# MIni_Quadcopter.net
KiCad netlist of a schematic drawn in Altium Designer
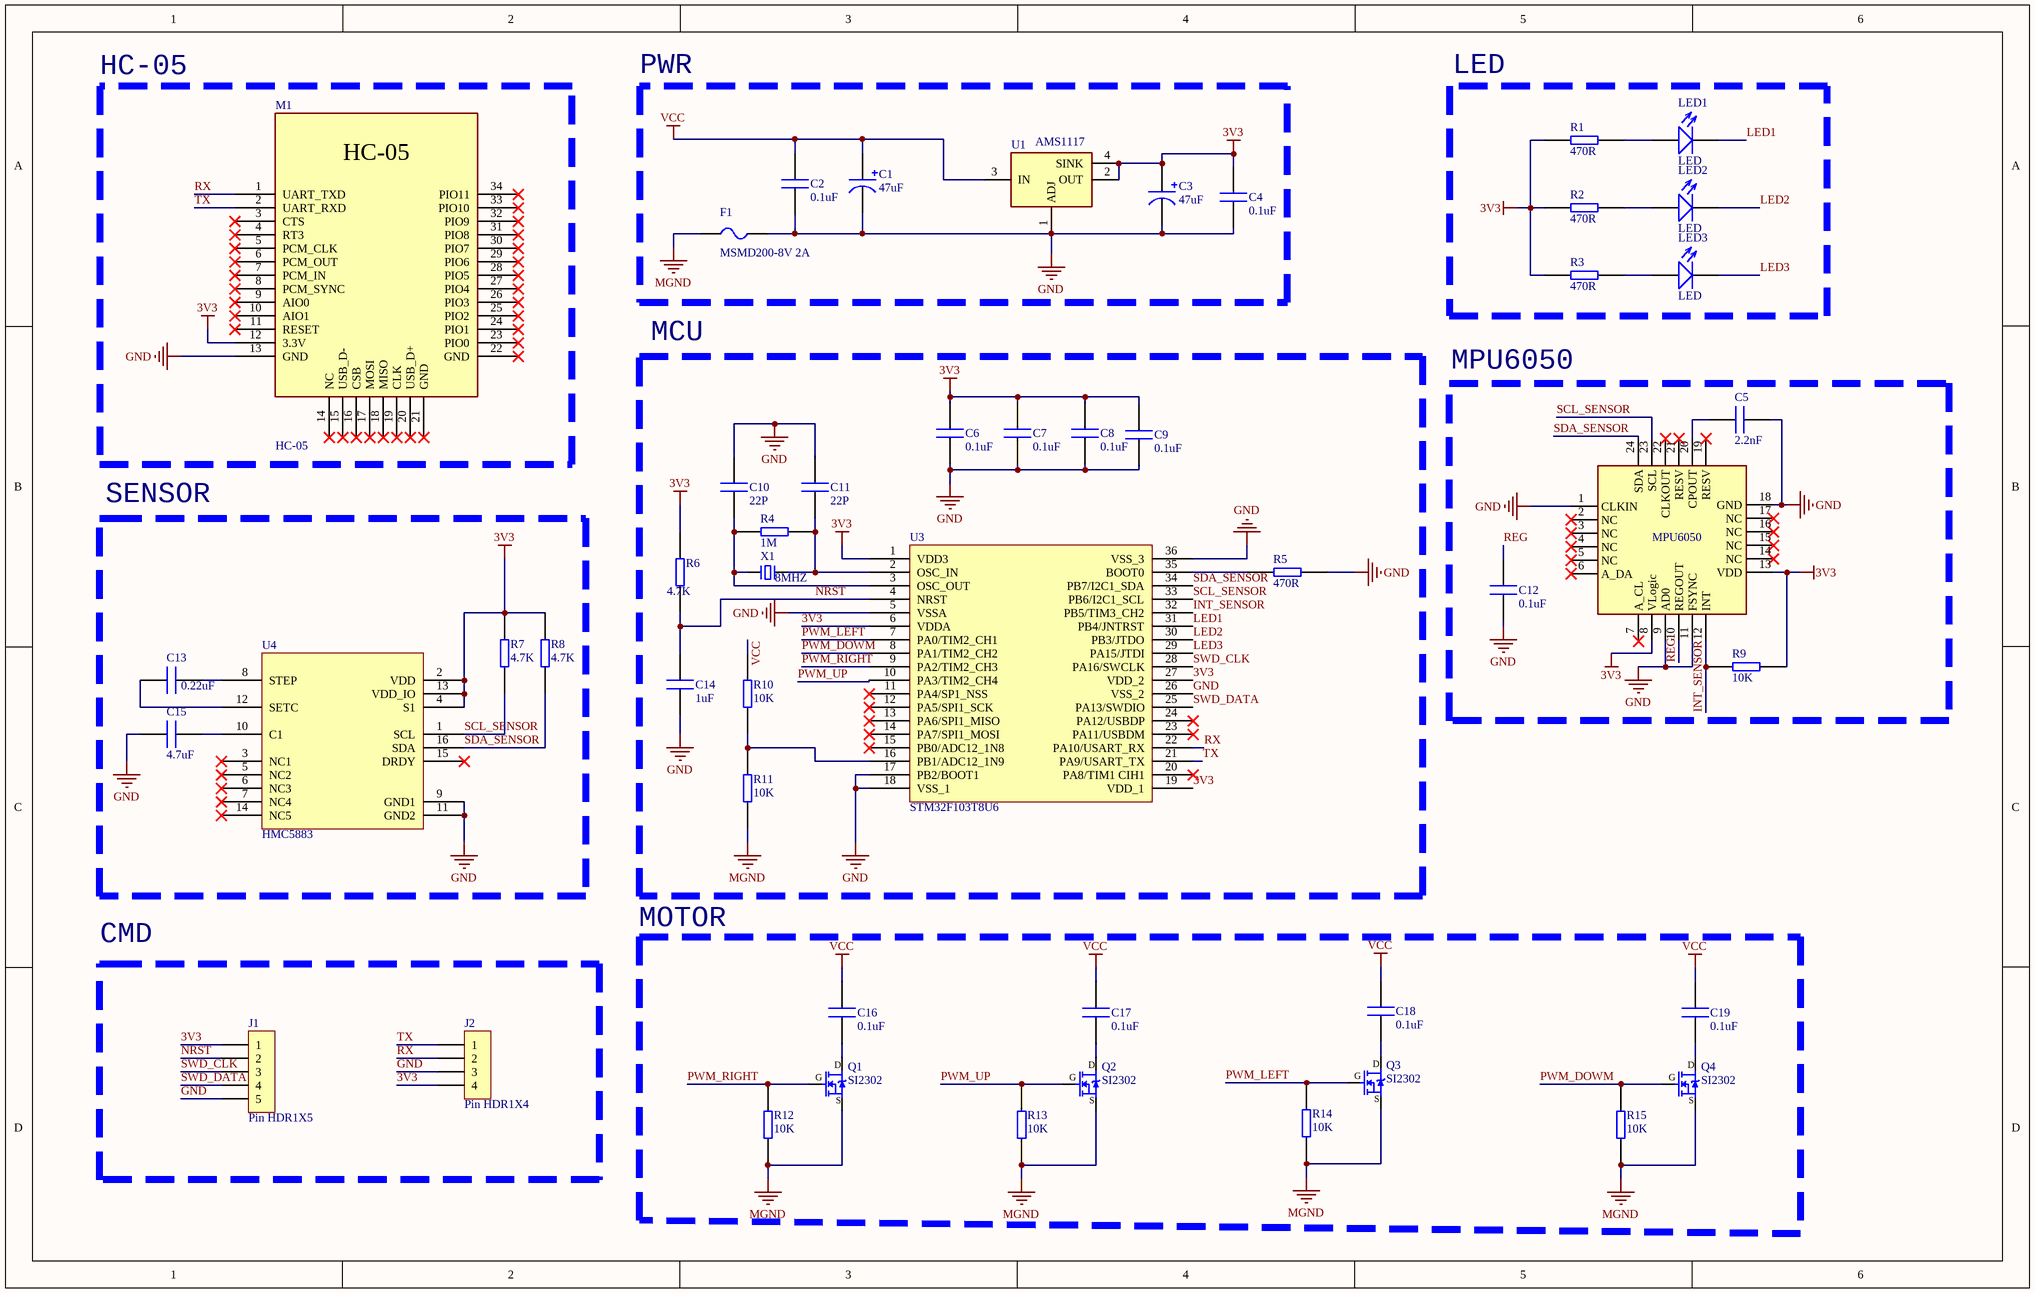
[diagram p0: MIni_Quadcopter.SchDoc]

(export (version "E")
  (design (tool "Eeschema 10.0.6"))
  (components
    (comp (ref "C1")
      (value "47uF")
      (footprint "Cap_SMD_5*5.4mm")
      (description "极性电容")
      (libsource (lib "COMMON") (part "Cap2"))
    )
    (comp (ref "C2")
      (value "0.1uF")
      (footprint "C0603")
      (description "无极电容")
      (libsource (lib "COMMON") (part "Cap1"))
    )
    (comp (ref "C3")
      (value "47uF")
      (footprint "Cap_SMD_5*5.4mm")
      (description "极性电容")
      (libsource (lib "COMMON") (part "Cap2"))
    )
    (comp (ref "C4")
      (value "0.1uF")
      (footprint "C0603")
      (description "无极电容")
      (libsource (lib "COMMON") (part "Cap1"))
    )
    (comp (ref "C5")
      (value "2.2nF")
      (footprint "C0603")
      (description "无极电容")
      (libsource (lib "COMMON") (part "Cap1"))
    )
    (comp (ref "C6")
      (value "0.1uF")
      (footprint "C0603")
      (description "无极电容")
      (libsource (lib "COMMON") (part "Cap1"))
    )
    (comp (ref "C7")
      (value "0.1uF")
      (footprint "C0603")
      (description "无极电容")
      (libsource (lib "COMMON") (part "Cap1"))
    )
    (comp (ref "C8")
      (value "0.1uF")
      (footprint "C0603")
      (description "无极电容")
      (libsource (lib "COMMON") (part "Cap1"))
    )
    (comp (ref "C9")
      (value "0.1uF")
      (footprint "C0603")
      (description "无极电容")
      (libsource (lib "COMMON") (part "Cap1"))
    )
    (comp (ref "C10")
      (value "22P")
      (footprint "C0603")
      (description "无极电容")
      (libsource (lib "COMMON") (part "Cap1"))
    )
    (comp (ref "C11")
      (value "22P")
      (footprint "C0603")
      (description "无极电容")
      (libsource (lib "COMMON") (part "Cap1"))
    )
    (comp (ref "C12")
      (value "0.1uF")
      (footprint "C0603")
      (description "无极电容")
      (libsource (lib "COMMON") (part "Cap1"))
    )
    (comp (ref "C13")
      (value "0.22uF")
      (footprint "C0603")
      (description "无极电容")
      (libsource (lib "COMMON") (part "Cap1"))
    )
    (comp (ref "C14")
      (value "1uF")
      (footprint "C0603")
      (description "无极电容")
      (libsource (lib "COMMON") (part "Cap1"))
    )
    (comp (ref "C15")
      (value "4.7uF")
      (footprint "C0603")
      (description "无极电容")
      (libsource (lib "COMMON") (part "Cap1"))
    )
    (comp (ref "C16")
      (value "0.1uF")
      (footprint "C0603")
      (description "无极电容")
      (libsource (lib "COMMON") (part "Cap1"))
    )
    (comp (ref "C17")
      (value "0.1uF")
      (footprint "C0603")
      (description "无极电容")
      (libsource (lib "COMMON") (part "Cap1"))
    )
    (comp (ref "C18")
      (value "0.1uF")
      (footprint "C0603")
      (description "无极电容")
      (libsource (lib "COMMON") (part "Cap1"))
    )
    (comp (ref "C19")
      (value "0.1uF")
      (footprint "C0603")
      (description "无极电容")
      (libsource (lib "COMMON") (part "Cap1"))
    )
    (comp (ref "F1")
      (value "MSMD200-8V 2A")
      (footprint "FU 1206")
      (description "贴片保险丝")
      (libsource (lib "COMMON") (part "FU"))
    )
    (comp (ref "J1")
      (value "Pin HDR1X5")
      (footprint "Pin HDR1X5/2mm-W")
      (libsource (lib "COMMON") (part "Pin HDR1X5"))
    )
    (comp (ref "J2")
      (value "Pin HDR1X4")
      (footprint "Pin HDR1X4/2.54mm-S")
      (libsource (lib "COMMON") (part "Pin HDR1X4"))
    )
    (comp (ref "LED1")
      (value "LED")
      (footprint "LED_0603")
      (description "发光二极管")
      (libsource (lib "COMMON") (part "LED"))
    )
    (comp (ref "LED2")
      (value "LED")
      (footprint "LED_0603")
      (description "发光二极管")
      (libsource (lib "COMMON") (part "LED"))
    )
    (comp (ref "LED3")
      (value "LED")
      (footprint "LED_0603")
      (description "发光二极管")
      (libsource (lib "COMMON") (part "LED"))
    )
    (comp (ref "M1")
      (value "HC-05")
      (footprint "HC-05")
      (description "串口蓝牙模块")
      (fields (field (name "版权归属") "源创客"))
      (libsource (lib "COMMON") (part "HC-05"))
    )
    (comp (ref "Q1")
      (value "SI2302")
      (footprint "SOT_23")
      (description "N沟道 20V/3A")
      (fields (field (name "版权归属") "源创客"))
      (libsource (lib "COMMON") (part "SI2302"))
    )
    (comp (ref "Q2")
      (value "SI2302")
      (footprint "SOT_23")
      (description "N沟道 20V/3A")
      (fields (field (name "版权归属") "源创客"))
      (libsource (lib "COMMON") (part "SI2302"))
    )
    (comp (ref "Q3")
      (value "SI2302")
      (footprint "SOT_23")
      (description "N沟道 20V/3A")
      (fields (field (name "版权归属") "源创客"))
      (libsource (lib "COMMON") (part "SI2302"))
    )
    (comp (ref "Q4")
      (value "SI2302")
      (footprint "SOT_23")
      (description "N沟道 20V/3A")
      (fields (field (name "版权归属") "源创客"))
      (libsource (lib "COMMON") (part "SI2302"))
    )
    (comp (ref "R1")
      (value "470R")
      (footprint "R0603")
      (description "普通电阻")
      (libsource (lib "COMMON") (part "Res"))
    )
    (comp (ref "R2")
      (value "470R")
      (footprint "R0603")
      (description "普通电阻")
      (libsource (lib "COMMON") (part "Res"))
    )
    (comp (ref "R3")
      (value "470R")
      (footprint "R0603")
      (description "普通电阻")
      (libsource (lib "COMMON") (part "Res"))
    )
    (comp (ref "R4")
      (value "1M")
      (footprint "R0603")
      (description "普通电阻")
      (libsource (lib "COMMON") (part "Res"))
    )
    (comp (ref "R5")
      (value "470R")
      (footprint "R0603")
      (description "普通电阻")
      (libsource (lib "COMMON") (part "Res"))
    )
    (comp (ref "R6")
      (value "4.7K")
      (footprint "R0603")
      (description "普通电阻")
      (libsource (lib "COMMON") (part "Res"))
    )
    (comp (ref "R7")
      (value "4.7K")
      (footprint "R0603")
      (description "普通电阻")
      (libsource (lib "COMMON") (part "Res"))
    )
    (comp (ref "R8")
      (value "4.7K")
      (footprint "R0603")
      (description "普通电阻")
      (libsource (lib "COMMON") (part "Res"))
    )
    (comp (ref "R9")
      (value "10K")
      (footprint "R0603")
      (description "普通电阻")
      (libsource (lib "COMMON") (part "Res"))
    )
    (comp (ref "R10")
      (value "10K")
      (footprint "R0603")
      (description "普通电阻")
      (libsource (lib "COMMON") (part "Res"))
    )
    (comp (ref "R11")
      (value "10K")
      (footprint "R0603")
      (description "普通电阻")
      (libsource (lib "COMMON") (part "Res"))
    )
    (comp (ref "R12")
      (value "10K")
      (footprint "R0603")
      (description "普通电阻")
      (libsource (lib "COMMON") (part "Res"))
    )
    (comp (ref "R13")
      (value "10K")
      (footprint "R0603")
      (description "普通电阻")
      (libsource (lib "COMMON") (part "Res"))
    )
    (comp (ref "R14")
      (value "10K")
      (footprint "R0603")
      (description "普通电阻")
      (libsource (lib "COMMON") (part "Res"))
    )
    (comp (ref "R15")
      (value "10K")
      (footprint "R0603")
      (description "普通电阻")
      (libsource (lib "COMMON") (part "Res"))
    )
    (comp (ref "U1")
      (value "AMS1117")
      (footprint "SOT_223")
      (description "稳压电源芯片降压IC")
      (libsource (lib "IC") (part "AMS1117"))
    )
    (comp (ref "U2")
      (value "MPU6050")
      (footprint "QFN-24")
      (description "六轴传感器")
      (libsource (lib "IC") (part "MPU6050"))
    )
    (comp (ref "U3")
      (value "STM32F103T8U6")
      (footprint "VFQN36_M")
      (libsource (lib "MCU") (part "STM32F103T8U6"))
    )
    (comp (ref "U4")
      (value "HMC5883")
      (footprint "LGA-16")
      (description "地磁传感器")
      (libsource (lib "IC") (part "HMC5883"))
    )
    (comp (ref "X1")
      (value "8MHZ")
      (footprint "OSC HC-49S")
      (description "2脚无源脚晶振")
      (libsource (lib "COMMON") (part "XTAL-2P"))
    )
  )
  (nets
    (net (code "1") (name "/INT_SENSOR") (class "Default")
      (node (ref "R9") (pin "1") (pinfunction "1_1") (pintype "passive"))
      (node (ref "U2") (pin "12") (pinfunction "INT_12") (pintype "passive"))
      (node (ref "U3") (pin "32") (pinfunction "PB5/TIM3_CH2_32") (pintype "passive"))
    )
    (net (code "2") (name "/LED1") (class "Default")
      (node (ref "LED1") (pin "1") (pinfunction "1_1") (pintype "passive"))
      (node (ref "U3") (pin "31") (pinfunction "PB4/JNTRST_31") (pintype "passive"))
    )
    (net (code "3") (name "/LED2") (class "Default")
      (node (ref "LED2") (pin "1") (pinfunction "1_1") (pintype "passive"))
      (node (ref "U3") (pin "30") (pinfunction "PB3/JTDO_30") (pintype "passive"))
    )
    (net (code "4") (name "/LED3") (class "Default")
      (node (ref "LED3") (pin "1") (pinfunction "1_1") (pintype "passive"))
      (node (ref "U3") (pin "29") (pinfunction "PA15/JTDI_29") (pintype "passive"))
    )
    (net (code "5") (name "/NRST") (class "Default")
      (node (ref "C14") (pin "2") (pinfunction "2_2") (pintype "passive"))
      (node (ref "J1") (pin "2") (pinfunction "2_2") (pintype "passive"))
      (node (ref "R6") (pin "1") (pinfunction "1_1") (pintype "passive"))
      (node (ref "U3") (pin "4") (pinfunction "NRST_4") (pintype "passive"))
    )
    (net (code "6") (name "/PWM_DOWM") (class "Default")
      (node (ref "Q4") (pin "1") (pinfunction "G_1") (pintype "passive"))
      (node (ref "R15") (pin "2") (pinfunction "2_2") (pintype "passive"))
      (node (ref "U3") (pin "8") (pinfunction "PA1/TIM2_CH2_8") (pintype "passive"))
    )
    (net (code "7") (name "/PWM_LEFT") (class "Default")
      (node (ref "Q3") (pin "1") (pinfunction "G_1") (pintype "passive"))
      (node (ref "R14") (pin "2") (pinfunction "2_2") (pintype "passive"))
      (node (ref "U3") (pin "7") (pinfunction "PA0/TIM2_CH1_7") (pintype "passive"))
    )
    (net (code "8") (name "/PWM_RIGHT") (class "Default")
      (node (ref "Q1") (pin "1") (pinfunction "G_1") (pintype "passive"))
      (node (ref "R12") (pin "2") (pinfunction "2_2") (pintype "passive"))
      (node (ref "U3") (pin "9") (pinfunction "PA2/TIM2_CH3_9") (pintype "passive"))
    )
    (net (code "9") (name "/PWM_UP") (class "Default")
      (node (ref "Q2") (pin "1") (pinfunction "G_1") (pintype "passive"))
      (node (ref "R13") (pin "2") (pinfunction "2_2") (pintype "passive"))
      (node (ref "U3") (pin "10") (pinfunction "PA3/TIM2_CH4_10") (pintype "passive"))
    )
    (net (code "10") (name "/REG") (class "Default")
      (node (ref "C12") (pin "1") (pinfunction "1_1") (pintype "passive"))
      (node (ref "U2") (pin "10") (pinfunction "REGOUT_10") (pintype "passive"))
    )
    (net (code "11") (name "/RX") (class "Default")
      (node (ref "J2") (pin "2") (pinfunction "2_2") (pintype "passive"))
      (node (ref "M1") (pin "1") (pinfunction "UART_TXD_1") (pintype "passive"))
      (node (ref "U3") (pin "22") (pinfunction "PA10/USART_RX_22") (pintype "passive"))
    )
    (net (code "12") (name "/SCL_SENSOR") (class "Default")
      (node (ref "R7") (pin "1") (pinfunction "1_1") (pintype "passive"))
      (node (ref "U2") (pin "23") (pinfunction "SCL_23") (pintype "passive"))
      (node (ref "U3") (pin "33") (pinfunction "PB6/I2C1_SCL_33") (pintype "passive"))
      (node (ref "U4") (pin "1") (pinfunction "SCL_1") (pintype "passive"))
    )
    (net (code "13") (name "/SDA_SENSOR") (class "Default")
      (node (ref "R8") (pin "1") (pinfunction "1_1") (pintype "passive"))
      (node (ref "U2") (pin "24") (pinfunction "SDA_24") (pintype "passive"))
      (node (ref "U3") (pin "34") (pinfunction "PB7/I2C1_SDA_34") (pintype "passive"))
      (node (ref "U4") (pin "16") (pinfunction "SDA_16") (pintype "passive"))
    )
    (net (code "14") (name "/SWD_CLK") (class "Default")
      (node (ref "J1") (pin "3") (pinfunction "3_3") (pintype "passive"))
      (node (ref "U3") (pin "28") (pinfunction "PA16/SWCLK_28") (pintype "passive"))
    )
    (net (code "15") (name "/SWD_DATA") (class "Default")
      (node (ref "J1") (pin "4") (pinfunction "4_4") (pintype "passive"))
      (node (ref "U3") (pin "25") (pinfunction "PA13/SWDIO_25") (pintype "passive"))
    )
    (net (code "16") (name "/TX") (class "Default")
      (node (ref "J2") (pin "1") (pinfunction "1_1") (pintype "passive"))
      (node (ref "M1") (pin "2") (pinfunction "UART_RXD_2") (pintype "passive"))
      (node (ref "U3") (pin "21") (pinfunction "PA9/USART_TX_21") (pintype "passive"))
    )
    (net (code "17") (name "3V3") (class "Default")
      (node (ref "C3") (pin "1") (pinfunction "1_1") (pintype "passive"))
      (node (ref "C4") (pin "2") (pinfunction "2_2") (pintype "passive"))
      (node (ref "C6") (pin "2") (pinfunction "2_2") (pintype "passive"))
      (node (ref "C7") (pin "2") (pinfunction "2_2") (pintype "passive"))
      (node (ref "C8") (pin "2") (pinfunction "2_2") (pintype "passive"))
      (node (ref "C9") (pin "2") (pinfunction "2_2") (pintype "passive"))
      (node (ref "J1") (pin "1") (pinfunction "1_1") (pintype "passive"))
      (node (ref "J2") (pin "4") (pinfunction "4_4") (pintype "passive"))
      (node (ref "M1") (pin "12") (pinfunction "3.3V_12") (pintype "passive"))
      (node (ref "R1") (pin "1") (pinfunction "1_1") (pintype "passive"))
      (node (ref "R2") (pin "1") (pinfunction "1_1") (pintype "passive"))
      (node (ref "R3") (pin "1") (pinfunction "1_1") (pintype "passive"))
      (node (ref "R6") (pin "2") (pinfunction "2_2") (pintype "passive"))
      (node (ref "R7") (pin "2") (pinfunction "2_2") (pintype "passive"))
      (node (ref "R8") (pin "2") (pinfunction "2_2") (pintype "passive"))
      (node (ref "R9") (pin "2") (pinfunction "2_2") (pintype "passive"))
      (node (ref "U1") (pin "2") (pinfunction "OUT_2") (pintype "passive"))
      (node (ref "U1") (pin "4") (pinfunction "SINK_4") (pintype "passive"))
      (node (ref "U2") (pin "13") (pinfunction "VDD_13") (pintype "passive"))
      (node (ref "U2") (pin "8") (pinfunction "VLogic_8") (pintype "passive"))
      (node (ref "U3") (pin "1") (pinfunction "VDD3_1") (pintype "passive"))
      (node (ref "U3") (pin "19") (pinfunction "VDD_1_19") (pintype "passive"))
      (node (ref "U3") (pin "27") (pinfunction "VDD_2_27") (pintype "passive"))
      (node (ref "U3") (pin "6") (pinfunction "VDDA_6") (pintype "passive"))
      (node (ref "U4") (pin "13") (pinfunction "VDD_IO_13") (pintype "passive"))
      (node (ref "U4") (pin "2") (pinfunction "VDD_2") (pintype "passive"))
      (node (ref "U4") (pin "4") (pinfunction "S1_4") (pintype "passive"))
    )
    (net (code "18") (name "GND") (class "Default")
      (node (ref "C1") (pin "2") (pinfunction "2_2") (pintype "passive"))
      (node (ref "C10") (pin "2") (pinfunction "2_2") (pintype "passive"))
      (node (ref "C11") (pin "2") (pinfunction "2_2") (pintype "passive"))
      (node (ref "C12") (pin "2") (pinfunction "2_2") (pintype "passive"))
      (node (ref "C14") (pin "1") (pinfunction "1_1") (pintype "passive"))
      (node (ref "C15") (pin "1") (pinfunction "1_1") (pintype "passive"))
      (node (ref "C2") (pin "1") (pinfunction "1_1") (pintype "passive"))
      (node (ref "C3") (pin "2") (pinfunction "2_2") (pintype "passive"))
      (node (ref "C4") (pin "1") (pinfunction "1_1") (pintype "passive"))
      (node (ref "C5") (pin "2") (pinfunction "2_2") (pintype "passive"))
      (node (ref "C6") (pin "1") (pinfunction "1_1") (pintype "passive"))
      (node (ref "C7") (pin "1") (pinfunction "1_1") (pintype "passive"))
      (node (ref "C8") (pin "1") (pinfunction "1_1") (pintype "passive"))
      (node (ref "C9") (pin "1") (pinfunction "1_1") (pintype "passive"))
      (node (ref "F1") (pin "2") (pinfunction "2_2") (pintype "passive"))
      (node (ref "J1") (pin "5") (pinfunction "5_5") (pintype "passive"))
      (node (ref "J2") (pin "3") (pinfunction "3_3") (pintype "passive"))
      (node (ref "M1") (pin "13") (pinfunction "GND_13") (pintype "passive"))
      (node (ref "R5") (pin "2") (pinfunction "2_2") (pintype "passive"))
      (node (ref "U1") (pin "1") (pinfunction "ADJ_1") (pintype "passive"))
      (node (ref "U2") (pin "1") (pinfunction "CLKIN_1") (pintype "passive"))
      (node (ref "U2") (pin "11") (pinfunction "FSYNC_11") (pintype "passive"))
      (node (ref "U2") (pin "18") (pinfunction "GND_18") (pintype "passive"))
      (node (ref "U2") (pin "9") (pinfunction "AD0_9") (pintype "passive"))
      (node (ref "U3") (pin "17") (pinfunction "PB2/BOOT1_17") (pintype "passive"))
      (node (ref "U3") (pin "18") (pinfunction "VSS_1_18") (pintype "passive"))
      (node (ref "U3") (pin "26") (pinfunction "VSS_2_26") (pintype "passive"))
      (node (ref "U3") (pin "36") (pinfunction "VSS_3_36") (pintype "passive"))
      (node (ref "U3") (pin "5") (pinfunction "VSSA_5") (pintype "passive"))
      (node (ref "U4") (pin "11") (pinfunction "GND2_11") (pintype "passive"))
      (node (ref "U4") (pin "9") (pinfunction "GND1_9") (pintype "passive"))
    )
    (net (code "19") (name "MGND") (class "Default")
      (node (ref "F1") (pin "1") (pinfunction "1_1") (pintype "passive"))
      (node (ref "Q1") (pin "2") (pinfunction "S_2") (pintype "passive"))
      (node (ref "Q2") (pin "2") (pinfunction "S_2") (pintype "passive"))
      (node (ref "Q3") (pin "2") (pinfunction "S_2") (pintype "passive"))
      (node (ref "Q4") (pin "2") (pinfunction "S_2") (pintype "passive"))
      (node (ref "R11") (pin "2") (pinfunction "2_2") (pintype "passive"))
      (node (ref "R12") (pin "1") (pinfunction "1_1") (pintype "passive"))
      (node (ref "R13") (pin "1") (pinfunction "1_1") (pintype "passive"))
      (node (ref "R14") (pin "1") (pinfunction "1_1") (pintype "passive"))
      (node (ref "R15") (pin "1") (pinfunction "1_1") (pintype "passive"))
    )
    (net (code "20") (name "Net-(LED1-Pad2)") (class "Default")
      (node (ref "LED1") (pin "2") (pinfunction "2_2") (pintype "passive"))
      (node (ref "R1") (pin "2") (pinfunction "2_2") (pintype "passive"))
    )
    (net (code "21") (name "Net-(LED2-Pad2)") (class "Default")
      (node (ref "LED2") (pin "2") (pinfunction "2_2") (pintype "passive"))
      (node (ref "R2") (pin "2") (pinfunction "2_2") (pintype "passive"))
    )
    (net (code "22") (name "Net-(LED3-Pad2)") (class "Default")
      (node (ref "LED3") (pin "2") (pinfunction "2_2") (pintype "passive"))
      (node (ref "R3") (pin "2") (pinfunction "2_2") (pintype "passive"))
    )
    (net (code "23") (name "Net-(Q1-D)") (class "Default")
      (node (ref "C16") (pin "1") (pinfunction "1_1") (pintype "passive"))
      (node (ref "Q1") (pin "3") (pinfunction "D_3") (pintype "passive"))
    )
    (net (code "24") (name "Net-(Q2-D)") (class "Default")
      (node (ref "C17") (pin "1") (pinfunction "1_1") (pintype "passive"))
      (node (ref "Q2") (pin "3") (pinfunction "D_3") (pintype "passive"))
    )
    (net (code "25") (name "Net-(Q3-D)") (class "Default")
      (node (ref "C18") (pin "1") (pinfunction "1_1") (pintype "passive"))
      (node (ref "Q3") (pin "3") (pinfunction "D_3") (pintype "passive"))
    )
    (net (code "26") (name "Net-(Q4-D)") (class "Default")
      (node (ref "C19") (pin "1") (pinfunction "1_1") (pintype "passive"))
      (node (ref "Q4") (pin "3") (pinfunction "D_3") (pintype "passive"))
    )
    (net (code "27") (name "Net-(U2-CPOUT)") (class "Default")
      (node (ref "C5") (pin "1") (pinfunction "1_1") (pintype "passive"))
      (node (ref "U2") (pin "20") (pinfunction "CPOUT_20") (pintype "passive"))
    )
    (net (code "28") (name "Net-(U3-BOOT0)") (class "Default")
      (node (ref "R5") (pin "1") (pinfunction "1_1") (pintype "passive"))
      (node (ref "U3") (pin "35") (pinfunction "BOOT0_35") (pintype "passive"))
    )
    (net (code "29") (name "Net-(U3-OSC_IN)") (class "Default")
      (node (ref "C11") (pin "1") (pinfunction "1_1") (pintype "passive"))
      (node (ref "R4") (pin "2") (pinfunction "2_2") (pintype "passive"))
      (node (ref "U3") (pin "2") (pinfunction "OSC_IN_2") (pintype "passive"))
      (node (ref "X1") (pin "2") (pinfunction "2_2") (pintype "passive"))
    )
    (net (code "30") (name "Net-(U3-OSC_OUT)") (class "Default")
      (node (ref "C10") (pin "1") (pinfunction "1_1") (pintype "passive"))
      (node (ref "R4") (pin "1") (pinfunction "1_1") (pintype "passive"))
      (node (ref "U3") (pin "3") (pinfunction "OSC_OUT_3") (pintype "passive"))
      (node (ref "X1") (pin "1") (pinfunction "1_1") (pintype "passive"))
    )
    (net (code "31") (name "Net-(U3-PB1{slash}ADC12_1N9)") (class "Default")
      (node (ref "R10") (pin "2") (pinfunction "2_2") (pintype "passive"))
      (node (ref "R11") (pin "1") (pinfunction "1_1") (pintype "passive"))
      (node (ref "U3") (pin "16") (pinfunction "PB1/ADC12_1N9_16") (pintype "passive"))
    )
    (net (code "32") (name "Net-(U4-C1)") (class "Default")
      (node (ref "C15") (pin "2") (pinfunction "2_2") (pintype "passive"))
      (node (ref "U4") (pin "10") (pinfunction "C1_10") (pintype "passive"))
    )
    (net (code "33") (name "Net-(U4-SETC)") (class "Default")
      (node (ref "C13") (pin "2") (pinfunction "2_2") (pintype "passive"))
      (node (ref "U4") (pin "12") (pinfunction "SETC_12") (pintype "passive"))
    )
    (net (code "34") (name "Net-(U4-STEP)") (class "Default")
      (node (ref "C13") (pin "1") (pinfunction "1_1") (pintype "passive"))
      (node (ref "U4") (pin "8") (pinfunction "STEP_8") (pintype "passive"))
    )
    (net (code "35") (name "VCC") (class "Default")
      (node (ref "C1") (pin "1") (pinfunction "1_1") (pintype "passive"))
      (node (ref "C16") (pin "2") (pinfunction "2_2") (pintype "passive"))
      (node (ref "C17") (pin "2") (pinfunction "2_2") (pintype "passive"))
      (node (ref "C18") (pin "2") (pinfunction "2_2") (pintype "passive"))
      (node (ref "C19") (pin "2") (pinfunction "2_2") (pintype "passive"))
      (node (ref "C2") (pin "2") (pinfunction "2_2") (pintype "passive"))
      (node (ref "R10") (pin "1") (pinfunction "1_1") (pintype "passive"))
      (node (ref "U1") (pin "3") (pinfunction "IN_3") (pintype "passive"))
    )
    (net (code "36") (name "unconnected-(M1-AIO0-Pad9)") (class "Default")
      (node (ref "M1") (pin "9") (pinfunction "AIO0_9") (pintype "passive+no_connect"))
    )
    (net (code "37") (name "unconnected-(M1-AIO1-Pad10)") (class "Default")
      (node (ref "M1") (pin "10") (pinfunction "AIO1_10") (pintype "passive+no_connect"))
    )
    (net (code "38") (name "unconnected-(M1-CLK-Pad19)") (class "Default")
      (node (ref "M1") (pin "19") (pinfunction "CLK_19") (pintype "passive+no_connect"))
    )
    (net (code "39") (name "unconnected-(M1-CSB-Pad16)") (class "Default")
      (node (ref "M1") (pin "16") (pinfunction "CSB_16") (pintype "passive+no_connect"))
    )
    (net (code "40") (name "unconnected-(M1-CTS-Pad3)") (class "Default")
      (node (ref "M1") (pin "3") (pinfunction "CTS_3") (pintype "passive+no_connect"))
    )
    (net (code "41") (name "unconnected-(M1-GND-Pad21)") (class "Default")
      (node (ref "M1") (pin "21") (pinfunction "GND_21") (pintype "passive+no_connect"))
    )
    (net (code "42") (name "unconnected-(M1-GND-Pad22)") (class "Default")
      (node (ref "M1") (pin "22") (pinfunction "GND_22") (pintype "passive+no_connect"))
    )
    (net (code "43") (name "unconnected-(M1-MISO-Pad18)") (class "Default")
      (node (ref "M1") (pin "18") (pinfunction "MISO_18") (pintype "passive+no_connect"))
    )
    (net (code "44") (name "unconnected-(M1-MOSI-Pad17)") (class "Default")
      (node (ref "M1") (pin "17") (pinfunction "MOSI_17") (pintype "passive+no_connect"))
    )
    (net (code "45") (name "unconnected-(M1-NC-Pad14)") (class "Default")
      (node (ref "M1") (pin "14") (pinfunction "NC_14") (pintype "passive+no_connect"))
    )
    (net (code "46") (name "unconnected-(M1-PCM_CLK-Pad5)") (class "Default")
      (node (ref "M1") (pin "5") (pinfunction "PCM_CLK_5") (pintype "passive+no_connect"))
    )
    (net (code "47") (name "unconnected-(M1-PCM_IN-Pad7)") (class "Default")
      (node (ref "M1") (pin "7") (pinfunction "PCM_IN_7") (pintype "passive+no_connect"))
    )
    (net (code "48") (name "unconnected-(M1-PCM_OUT-Pad6)") (class "Default")
      (node (ref "M1") (pin "6") (pinfunction "PCM_OUT_6") (pintype "passive+no_connect"))
    )
    (net (code "49") (name "unconnected-(M1-PCM_SYNC-Pad8)") (class "Default")
      (node (ref "M1") (pin "8") (pinfunction "PCM_SYNC_8") (pintype "passive+no_connect"))
    )
    (net (code "50") (name "unconnected-(M1-PIO0-Pad23)") (class "Default")
      (node (ref "M1") (pin "23") (pinfunction "PIO0_23") (pintype "passive+no_connect"))
    )
    (net (code "51") (name "unconnected-(M1-PIO1-Pad24)") (class "Default")
      (node (ref "M1") (pin "24") (pinfunction "PIO1_24") (pintype "passive+no_connect"))
    )
    (net (code "52") (name "unconnected-(M1-PIO2-Pad25)") (class "Default")
      (node (ref "M1") (pin "25") (pinfunction "PIO2_25") (pintype "passive+no_connect"))
    )
    (net (code "53") (name "unconnected-(M1-PIO3-Pad26)") (class "Default")
      (node (ref "M1") (pin "26") (pinfunction "PIO3_26") (pintype "passive+no_connect"))
    )
    (net (code "54") (name "unconnected-(M1-PIO4-Pad27)") (class "Default")
      (node (ref "M1") (pin "27") (pinfunction "PIO4_27") (pintype "passive+no_connect"))
    )
    (net (code "55") (name "unconnected-(M1-PIO5-Pad28)") (class "Default")
      (node (ref "M1") (pin "28") (pinfunction "PIO5_28") (pintype "passive+no_connect"))
    )
    (net (code "56") (name "unconnected-(M1-PIO6-Pad29)") (class "Default")
      (node (ref "M1") (pin "29") (pinfunction "PIO6_29") (pintype "passive+no_connect"))
    )
    (net (code "57") (name "unconnected-(M1-PIO7-Pad30)") (class "Default")
      (node (ref "M1") (pin "30") (pinfunction "PIO7_30") (pintype "passive+no_connect"))
    )
    (net (code "58") (name "unconnected-(M1-PIO8-Pad31)") (class "Default")
      (node (ref "M1") (pin "31") (pinfunction "PIO8_31") (pintype "passive+no_connect"))
    )
    (net (code "59") (name "unconnected-(M1-PIO9-Pad32)") (class "Default")
      (node (ref "M1") (pin "32") (pinfunction "PIO9_32") (pintype "passive+no_connect"))
    )
    (net (code "60") (name "unconnected-(M1-PIO10-Pad33)") (class "Default")
      (node (ref "M1") (pin "33") (pinfunction "PIO10_33") (pintype "passive+no_connect"))
    )
    (net (code "61") (name "unconnected-(M1-PIO11-Pad34)") (class "Default")
      (node (ref "M1") (pin "34") (pinfunction "PIO11_34") (pintype "passive+no_connect"))
    )
    (net (code "62") (name "unconnected-(M1-RESET-Pad11)") (class "Default")
      (node (ref "M1") (pin "11") (pinfunction "RESET_11") (pintype "passive+no_connect"))
    )
    (net (code "63") (name "unconnected-(M1-RT3-Pad4)") (class "Default")
      (node (ref "M1") (pin "4") (pinfunction "RT3_4") (pintype "passive+no_connect"))
    )
    (net (code "64") (name "unconnected-(M1-USB_D+-Pad20)") (class "Default")
      (node (ref "M1") (pin "20") (pinfunction "USB_D+_20") (pintype "passive+no_connect"))
    )
    (net (code "65") (name "unconnected-(M1-USB_D--Pad15)") (class "Default")
      (node (ref "M1") (pin "15") (pinfunction "USB_D-_15") (pintype "passive+no_connect"))
    )
    (net (code "66") (name "unconnected-(U2-A_CL-Pad7)") (class "Default")
      (node (ref "U2") (pin "7") (pinfunction "A_CL_7") (pintype "passive+no_connect"))
    )
    (net (code "67") (name "unconnected-(U2-A_DA-Pad6)") (class "Default")
      (node (ref "U2") (pin "6") (pinfunction "A_DA_6") (pintype "passive+no_connect"))
    )
    (net (code "68") (name "unconnected-(U2-CLKOUT-Pad22)") (class "Default")
      (node (ref "U2") (pin "22") (pinfunction "CLKOUT_22") (pintype "passive+no_connect"))
    )
    (net (code "69") (name "unconnected-(U2-NC-Pad2)") (class "Default")
      (node (ref "U2") (pin "2") (pinfunction "NC_2") (pintype "passive+no_connect"))
    )
    (net (code "70") (name "unconnected-(U2-NC-Pad3)") (class "Default")
      (node (ref "U2") (pin "3") (pinfunction "NC_3") (pintype "passive+no_connect"))
    )
    (net (code "71") (name "unconnected-(U2-NC-Pad4)") (class "Default")
      (node (ref "U2") (pin "4") (pinfunction "NC_4") (pintype "passive+no_connect"))
    )
    (net (code "72") (name "unconnected-(U2-NC-Pad5)") (class "Default")
      (node (ref "U2") (pin "5") (pinfunction "NC_5") (pintype "passive+no_connect"))
    )
    (net (code "73") (name "unconnected-(U2-NC-Pad14)") (class "Default")
      (node (ref "U2") (pin "14") (pinfunction "NC_14") (pintype "passive+no_connect"))
    )
    (net (code "74") (name "unconnected-(U2-NC-Pad15)") (class "Default")
      (node (ref "U2") (pin "15") (pinfunction "NC_15") (pintype "passive+no_connect"))
    )
    (net (code "75") (name "unconnected-(U2-NC-Pad16)") (class "Default")
      (node (ref "U2") (pin "16") (pinfunction "NC_16") (pintype "passive+no_connect"))
    )
    (net (code "76") (name "unconnected-(U2-NC-Pad17)") (class "Default")
      (node (ref "U2") (pin "17") (pinfunction "NC_17") (pintype "passive+no_connect"))
    )
    (net (code "77") (name "unconnected-(U2-RESV-Pad19)") (class "Default")
      (node (ref "U2") (pin "19") (pinfunction "RESV_19") (pintype "passive+no_connect"))
    )
    (net (code "78") (name "unconnected-(U2-RESV-Pad21)") (class "Default")
      (node (ref "U2") (pin "21") (pinfunction "RESV_21") (pintype "passive+no_connect"))
    )
    (net (code "79") (name "unconnected-(U3-PA4{slash}SP1_NSS-Pad11)") (class "Default")
      (node (ref "U3") (pin "11") (pinfunction "PA4/SP1_NSS_11") (pintype "passive+no_connect"))
    )
    (net (code "80") (name "unconnected-(U3-PA5{slash}SPI1_SCK-Pad12)") (class "Default")
      (node (ref "U3") (pin "12") (pinfunction "PA5/SPI1_SCK_12") (pintype "passive+no_connect"))
    )
    (net (code "81") (name "unconnected-(U3-PA6{slash}SPI1_MISO-Pad13)") (class "Default")
      (node (ref "U3") (pin "13") (pinfunction "PA6/SPI1_MISO_13") (pintype "passive+no_connect"))
    )
    (net (code "82") (name "unconnected-(U3-PA7{slash}SPI1_MOSI-Pad14)") (class "Default")
      (node (ref "U3") (pin "14") (pinfunction "PA7/SPI1_MOSI_14") (pintype "passive+no_connect"))
    )
    (net (code "83") (name "unconnected-(U3-PA8{slash}TIM1_CIH1-Pad20)") (class "Default")
      (node (ref "U3") (pin "20") (pinfunction "PA8/TIM1_CIH1_20") (pintype "passive+no_connect"))
    )
    (net (code "84") (name "unconnected-(U3-PA11{slash}USBDM-Pad23)") (class "Default")
      (node (ref "U3") (pin "23") (pinfunction "PA11/USBDM_23") (pintype "passive+no_connect"))
    )
    (net (code "85") (name "unconnected-(U3-PA12{slash}USBDP-Pad24)") (class "Default")
      (node (ref "U3") (pin "24") (pinfunction "PA12/USBDP_24") (pintype "passive+no_connect"))
    )
    (net (code "86") (name "unconnected-(U3-PB0{slash}ADC12_1N8-Pad15)") (class "Default")
      (node (ref "U3") (pin "15") (pinfunction "PB0/ADC12_1N8_15") (pintype "passive+no_connect"))
    )
    (net (code "87") (name "unconnected-(U4-DRDY-Pad15)") (class "Default")
      (node (ref "U4") (pin "15") (pinfunction "DRDY_15") (pintype "passive+no_connect"))
    )
    (net (code "88") (name "unconnected-(U4-NC1-Pad3)") (class "Default")
      (node (ref "U4") (pin "3") (pinfunction "NC1_3") (pintype "passive+no_connect"))
    )
    (net (code "89") (name "unconnected-(U4-NC2-Pad5)") (class "Default")
      (node (ref "U4") (pin "5") (pinfunction "NC2_5") (pintype "passive+no_connect"))
    )
    (net (code "90") (name "unconnected-(U4-NC3-Pad6)") (class "Default")
      (node (ref "U4") (pin "6") (pinfunction "NC3_6") (pintype "passive+no_connect"))
    )
    (net (code "91") (name "unconnected-(U4-NC4-Pad7)") (class "Default")
      (node (ref "U4") (pin "7") (pinfunction "NC4_7") (pintype "passive+no_connect"))
    )
    (net (code "92") (name "unconnected-(U4-NC5-Pad14)") (class "Default")
      (node (ref "U4") (pin "14") (pinfunction "NC5_14") (pintype "passive+no_connect"))
    )
  )
)
